# OpenBook_v28.net
KiCad netlist of a schematic drawn in EAGLE
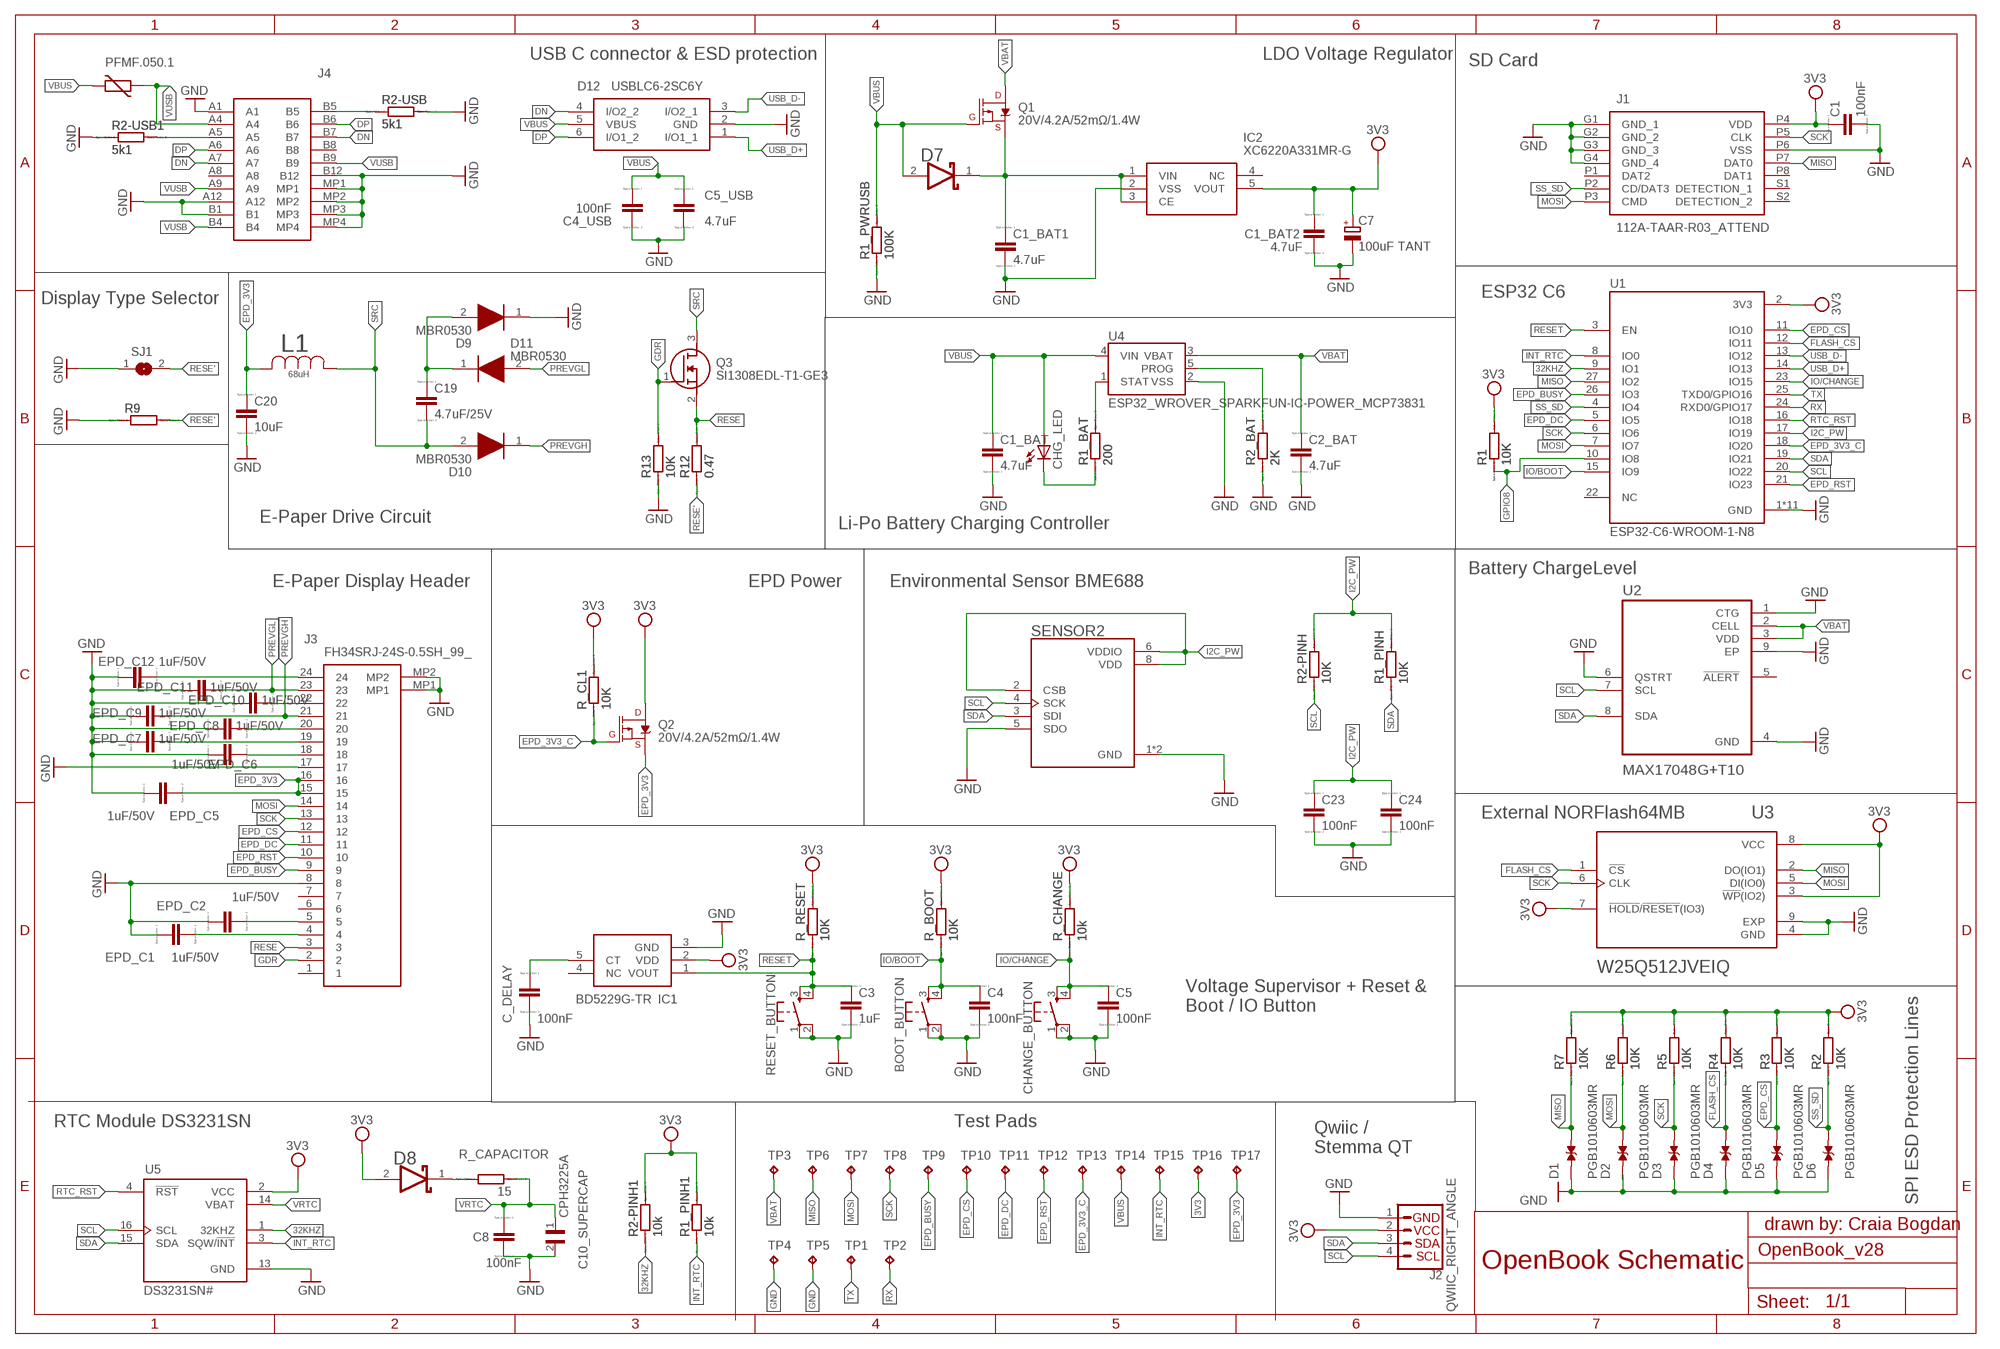
[diagram p0: schematic, sheet 1]

(export (version "E")
  (design (tool "Eeschema 10.0.6"))
  (components
    (comp (ref "BOOT_BUTTON")
      (value "BUTTON_CUSYOMV1")
      (footprint "eagle-import:MYBUTTON")
      (libsource (lib "eagle-import") (part "BUTTON_CUSYOMV1"))
    )
    (comp (ref "C1")
      (value "100nF")
      (footprint "eagle-import:EAGLE-LTSPICE_C0402")
      (libsource (lib "eagle-import") (part "EAGLE-LTSPICE_CC0402"))
    )
    (comp (ref "C1_BAT")
      (value "4.7uF")
      (footprint "eagle-import:EAGLE-LTSPICE_C0402")
      (libsource (lib "eagle-import") (part "EAGLE-LTSPICE_CC0402"))
    )
    (comp (ref "C1_BAT1")
      (value "4.7uF")
      (footprint "eagle-import:EAGLE-LTSPICE_C0402")
      (libsource (lib "eagle-import") (part "EAGLE-LTSPICE_CC0402"))
    )
    (comp (ref "C1_BAT2")
      (value "4.7uF")
      (footprint "eagle-import:EAGLE-LTSPICE_C0402")
      (libsource (lib "eagle-import") (part "EAGLE-LTSPICE_CC0402"))
    )
    (comp (ref "C2_BAT")
      (value "4.7uF")
      (footprint "eagle-import:EAGLE-LTSPICE_C0402")
      (libsource (lib "eagle-import") (part "EAGLE-LTSPICE_CC0402"))
    )
    (comp (ref "C3")
      (value "1uF")
      (footprint "eagle-import:EAGLE-LTSPICE_C0402")
      (libsource (lib "eagle-import") (part "EAGLE-LTSPICE_CC0402"))
    )
    (comp (ref "C4")
      (value "100nF")
      (footprint "eagle-import:EAGLE-LTSPICE_C0402")
      (libsource (lib "eagle-import") (part "EAGLE-LTSPICE_CC0402"))
    )
    (comp (ref "C4_USB")
      (value "100nF")
      (footprint "eagle-import:EAGLE-LTSPICE_C0402")
      (libsource (lib "eagle-import") (part "EAGLE-LTSPICE_CC0402"))
    )
    (comp (ref "C5")
      (value "100nF")
      (footprint "eagle-import:EAGLE-LTSPICE_C0402")
      (libsource (lib "eagle-import") (part "EAGLE-LTSPICE_CC0402"))
    )
    (comp (ref "C5_USB")
      (value "4.7uF")
      (footprint "eagle-import:EAGLE-LTSPICE_C0402")
      (libsource (lib "eagle-import") (part "EAGLE-LTSPICE_CC0402"))
    )
    (comp (ref "C7")
      (value "100uF TANT")
      (footprint "eagle-import:RCL_CT3528")
      (libsource (lib "eagle-import") (part "RCL_CPOL-EUCT3528"))
    )
    (comp (ref "C8")
      (value "100nF")
      (footprint "eagle-import:EAGLE-LTSPICE_C0402")
      (libsource (lib "eagle-import") (part "EAGLE-LTSPICE_CC0402"))
    )
    (comp (ref "C10_SUPERCAP")
      (value "CPH3225A")
      (footprint "eagle-import:CAPCP3225X100N")
      (fields (field (name "MF") "Seiko Instruments"))
      (libsource (lib "eagle-import") (part "CPH3225A"))
    )
    (comp (ref "C19")
      (value "4.7uF/25V")
      (footprint "eagle-import:EAGLE-LTSPICE_C0402")
      (libsource (lib "eagle-import") (part "EAGLE-LTSPICE_CC0402"))
    )
    (comp (ref "C20")
      (value "10uF")
      (footprint "eagle-import:EAGLE-LTSPICE_C0402")
      (libsource (lib "eagle-import") (part "EAGLE-LTSPICE_CC0402"))
    )
    (comp (ref "C23")
      (value "100nF")
      (footprint "eagle-import:EAGLE-LTSPICE_C0402")
      (libsource (lib "eagle-import") (part "EAGLE-LTSPICE_CC0402"))
    )
    (comp (ref "C24")
      (value "100nF")
      (footprint "eagle-import:EAGLE-LTSPICE_C0402")
      (libsource (lib "eagle-import") (part "EAGLE-LTSPICE_CC0402"))
    )
    (comp (ref "CHANGE_BUTTON")
      (value "BUTTON_CUSYOMV1")
      (footprint "eagle-import:MYBUTTON")
      (libsource (lib "eagle-import") (part "BUTTON_CUSYOMV1"))
    )
    (comp (ref "CHG_LED")
      (value "ADAFRUIT_LEDCHIP-LED0603")
      (footprint "eagle-import:ADAFRUIT_CHIP-LED0603")
      (libsource (lib "eagle-import") (part "ADAFRUIT_LEDCHIP-LED0603"))
    )
    (comp (ref "C_DELAY")
      (value "100nF")
      (footprint "eagle-import:EAGLE-LTSPICE_C0402")
      (libsource (lib "eagle-import") (part "EAGLE-LTSPICE_CC0402"))
    )
    (comp (ref "D1")
      (value "PGB1010603MR")
      (footprint "eagle-import:DIOC1608X36N")
      (fields (field (name "MF") "Littelfuse Inc."))
      (libsource (lib "eagle-import") (part "PGB1010603MR"))
    )
    (comp (ref "D2")
      (value "PGB1010603MR")
      (footprint "eagle-import:DIOC1608X36N")
      (fields (field (name "MF") "Littelfuse Inc."))
      (libsource (lib "eagle-import") (part "PGB1010603MR"))
    )
    (comp (ref "D3")
      (value "PGB1010603MR")
      (footprint "eagle-import:DIOC1608X36N")
      (fields (field (name "MF") "Littelfuse Inc."))
      (libsource (lib "eagle-import") (part "PGB1010603MR"))
    )
    (comp (ref "D4")
      (value "PGB1010603MR")
      (footprint "eagle-import:DIOC1608X36N")
      (fields (field (name "MF") "Littelfuse Inc."))
      (libsource (lib "eagle-import") (part "PGB1010603MR"))
    )
    (comp (ref "D5")
      (value "PGB1010603MR")
      (footprint "eagle-import:DIOC1608X36N")
      (fields (field (name "MF") "Littelfuse Inc."))
      (libsource (lib "eagle-import") (part "PGB1010603MR"))
    )
    (comp (ref "D6")
      (value "PGB1010603MR")
      (footprint "eagle-import:DIOC1608X36N")
      (fields (field (name "MF") "Littelfuse Inc."))
      (libsource (lib "eagle-import") (part "PGB1010603MR"))
    )
    (comp (ref "D7")
      (value "ESP32_WROVER_AVX---SD0805S020S1R0_AVX_SD0805S020S1R0_0_0AVX_SD0805S020S1R0_0_0")
      (footprint "eagle-import:ESP32_WROVER_AVX---SD0805S020S1R0_AVX_SD0805S020S1R0_0")
      (fields
        (field (name "DIGIKEY_PART_NUMBER") "478-7800-1-ND")
        (field (name "MF") "AVX")
        (field (name "MOUSER_PART_NUMBER") "581-SD0805S020S1R0")
      )
      (libsource (lib "eagle-import") (part "ESP32_WROVER_AVX---SD0805S020S1R0_AVX_SD0805S020S1R0_0_0AVX_SD0805S020S1R0_0_0"))
    )
    (comp (ref "D8")
      (value "ESP32_WROVER_AVX---SD0805S020S1R0_AVX_SD0805S020S1R0_0_0AVX_SD0805S020S1R0_0_0")
      (footprint "eagle-import:ESP32_WROVER_AVX---SD0805S020S1R0_AVX_SD0805S020S1R0_0")
      (fields
        (field (name "DIGIKEY_PART_NUMBER") "478-7800-1-ND")
        (field (name "MF") "AVX")
        (field (name "MOUSER_PART_NUMBER") "581-SD0805S020S1R0")
      )
      (libsource (lib "eagle-import") (part "ESP32_WROVER_AVX---SD0805S020S1R0_AVX_SD0805S020S1R0_0_0AVX_SD0805S020S1R0_0_0"))
    )
    (comp (ref "D9")
      (value "MBR0530")
      (footprint "eagle-import:SOD3716X135N")
      (fields (field (name "MF") "ON Semiconductor"))
      (libsource (lib "eagle-import") (part "MBR0530"))
    )
    (comp (ref "D10")
      (value "MBR0530")
      (footprint "eagle-import:SOD3716X135N")
      (fields (field (name "MF") "ON Semiconductor"))
      (libsource (lib "eagle-import") (part "MBR0530"))
    )
    (comp (ref "D11")
      (value "MBR0530")
      (footprint "eagle-import:SOD3716X135N")
      (fields (field (name "MF") "ON Semiconductor"))
      (libsource (lib "eagle-import") (part "MBR0530"))
    )
    (comp (ref "D12")
      (value "USBLC6-2SC6Y")
      (footprint "eagle-import:SOT95P280X145-6N")
      (fields (field (name "MF") "STMicroelectronics"))
      (libsource (lib "eagle-import") (part "USBLC6-2SC6Y"))
    )
    (comp (ref "EPD_C1")
      (value "1uF/50V")
      (footprint "eagle-import:EAGLE-LTSPICE_C0402")
      (libsource (lib "eagle-import") (part "EAGLE-LTSPICE_CC0402"))
    )
    (comp (ref "EPD_C2")
      (value "1uF/50V")
      (footprint "eagle-import:EAGLE-LTSPICE_C0402")
      (libsource (lib "eagle-import") (part "EAGLE-LTSPICE_CC0402"))
    )
    (comp (ref "EPD_C5")
      (value "1uF/50V")
      (footprint "eagle-import:EAGLE-LTSPICE_C0402")
      (libsource (lib "eagle-import") (part "EAGLE-LTSPICE_CC0402"))
    )
    (comp (ref "EPD_C6")
      (value "1uF/50V")
      (footprint "eagle-import:EAGLE-LTSPICE_C0402")
      (libsource (lib "eagle-import") (part "EAGLE-LTSPICE_CC0402"))
    )
    (comp (ref "EPD_C7")
      (value "1uF/50V")
      (footprint "eagle-import:EAGLE-LTSPICE_C0402")
      (libsource (lib "eagle-import") (part "EAGLE-LTSPICE_CC0402"))
    )
    (comp (ref "EPD_C8")
      (value "1uF/50V")
      (footprint "eagle-import:EAGLE-LTSPICE_C0402")
      (libsource (lib "eagle-import") (part "EAGLE-LTSPICE_CC0402"))
    )
    (comp (ref "EPD_C9")
      (value "1uF/50V")
      (footprint "eagle-import:EAGLE-LTSPICE_C0402")
      (libsource (lib "eagle-import") (part "EAGLE-LTSPICE_CC0402"))
    )
    (comp (ref "EPD_C10")
      (value "1uF/50V")
      (footprint "eagle-import:EAGLE-LTSPICE_C0402")
      (libsource (lib "eagle-import") (part "EAGLE-LTSPICE_CC0402"))
    )
    (comp (ref "EPD_C11")
      (value "1uF/50V")
      (footprint "eagle-import:EAGLE-LTSPICE_C0402")
      (libsource (lib "eagle-import") (part "EAGLE-LTSPICE_CC0402"))
    )
    (comp (ref "EPD_C12")
      (value "1uF/50V")
      (footprint "eagle-import:EAGLE-LTSPICE_C0402")
      (libsource (lib "eagle-import") (part "EAGLE-LTSPICE_CC0402"))
    )
    (comp (ref "IC1")
      (value "BD5229G-TR")
      (footprint "eagle-import:SOT95P280X125-5N")
      (fields (field (name "MOUSER_PART_NUMBER") "755-BD5229G-TR"))
      (libsource (lib "eagle-import") (part "BD5229G-TR"))
    )
    (comp (ref "IC2")
      (value "XC6220A331MR-G")
      (footprint "eagle-import:SOT95P280X120-5N")
      (fields (field (name "MOUSER_PART_NUMBER") "865-XC6220A331MR-G"))
      (libsource (lib "eagle-import") (part "XC6220A331MR-G"))
    )
    (comp (ref "J1")
      (value "112A-TAAR-R03_ATTEND")
      (footprint "eagle-import:112ATAARR03ATTEND")
      (fields (field (name "MANUFACTURER_PART_NUMBER") "112A-TAAR-R03 ATTEND"))
      (libsource (lib "eagle-import") (part "112A-TAAR-R03_ATTEND"))
    )
    (comp (ref "J2")
      (value "QWIIC_RIGHT_ANGLE")
      (footprint "eagle-import:JST04_1MM_RA")
      (libsource (lib "eagle-import") (part "QWIIC_CONNECTORJS-1MM"))
    )
    (comp (ref "J3")
      (value "FH34SRJ-24S-0.5SH_99_")
      (footprint "eagle-import:FH34SRJ24S05SH99")
      (fields
        (field (name "MANUFACTURER_PART_NUMBER") "FH34SRJ-24S-0.5SH(99)")
        (field (name "MOUSER_PART_NUMBER") "798-FH34SRJ24S05SH99")
      )
      (libsource (lib "eagle-import") (part "FH34SRJ-24S-0.5SH_99_"))
    )
    (comp (ref "J4")
      (value "SAMACSYS_PARTS_USB4110-GF-A")
      (footprint "eagle-import:SAMACSYS_PARTS_USB4110GFA")
      (fields
        (field (name "MANUFACTURER_PART_NUMBER") "USB4110-GF-A")
        (field (name "MOUSER_PART_NUMBER") "640-USB4110-GF-A")
      )
      (libsource (lib "eagle-import") (part "SAMACSYS_PARTS_USB4110-GF-A"))
    )
    (comp (ref "L1")
      (value "68uH")
      (footprint "eagle-import:IND_4828-WE-TPC_WRE")
      (fields
        (field (name "MANUFACTURER_PART_NUMBER") "744043680")
        (field (name "COPYRIGHT") "Copyright (C) 2024 Ultra Librarian. All rights reserved.")
      )
      (libsource (lib "eagle-import") (part "744043680IND_4828-WE-TPC_WRE"))
    )
    (comp (ref "PFMF.050.1")
      (value "ESP32C6_VARISTORCN1812")
      (footprint "eagle-import:ESP32C6_VARISTOR_CT_CN1812")
      (libsource (lib "eagle-import") (part "ESP32C6_VARISTORCN1812"))
    )
    (comp (ref "Q1")
      (value "20V/4.2A/52mΩ/1.4W")
      (footprint "eagle-import:ESP32_WROVER_SPARKFUN-DISCRETESEMI_SOT23-3")
      (libsource (lib "eagle-import") (part "ESP32_WROVER_SPARKFUN-DISCRETESEMI_MOSFET_PCH-DMG2305UX-7"))
    )
    (comp (ref "Q2")
      (value "20V/4.2A/52mΩ/1.4W")
      (footprint "eagle-import:ESP32_WROVER_SPARKFUN-DISCRETESEMI_SOT23-3")
      (libsource (lib "eagle-import") (part "ESP32_WROVER_SPARKFUN-DISCRETESEMI_MOSFET_PCH-DMG2305UX-7"))
    )
    (comp (ref "Q3")
      (value "SI1308EDL-T1-GE3")
      (footprint "eagle-import:SOT65P210X110-3N")
      (fields (field (name "MF") "Vishay Siliconix"))
      (libsource (lib "eagle-import") (part "SI1308EDL-T1-GE3"))
    )
    (comp (ref "R1")
      (value "10K")
      (footprint "eagle-import:ESP32_WROVER_EAGLE-LTSPICE_R0402")
      (libsource (lib "eagle-import") (part "ESP32_WROVER_EAGLE-LTSPICE_RR0402"))
    )
    (comp (ref "R1_BAT")
      (value "200")
      (footprint "eagle-import:ESP32_WROVER_EAGLE-LTSPICE_R0402")
      (libsource (lib "eagle-import") (part "ESP32_WROVER_EAGLE-LTSPICE_RR0402"))
    )
    (comp (ref "R1_PINH")
      (value "10K")
      (footprint "eagle-import:ESP32_WROVER_EAGLE-LTSPICE_R0402")
      (libsource (lib "eagle-import") (part "ESP32_WROVER_EAGLE-LTSPICE_RR0402"))
    )
    (comp (ref "R1_PINH1")
      (value "10k")
      (footprint "eagle-import:ESP32_WROVER_EAGLE-LTSPICE_R0402")
      (libsource (lib "eagle-import") (part "ESP32_WROVER_EAGLE-LTSPICE_RR0402"))
    )
    (comp (ref "R1_PWRUSB")
      (value "100K")
      (footprint "eagle-import:ESP32_WROVER_EAGLE-LTSPICE_R0402")
      (libsource (lib "eagle-import") (part "ESP32_WROVER_EAGLE-LTSPICE_RR0402"))
    )
    (comp (ref "R2")
      (value "10K")
      (footprint "eagle-import:ESP32_WROVER_EAGLE-LTSPICE_R0402")
      (libsource (lib "eagle-import") (part "ESP32_WROVER_EAGLE-LTSPICE_RR0402"))
    )
    (comp (ref "R2-PINH")
      (value "10K")
      (footprint "eagle-import:ESP32_WROVER_EAGLE-LTSPICE_R0402")
      (libsource (lib "eagle-import") (part "ESP32_WROVER_EAGLE-LTSPICE_RR0402"))
    )
    (comp (ref "R2-PINH1")
      (value "10k")
      (footprint "eagle-import:ESP32_WROVER_EAGLE-LTSPICE_R0402")
      (libsource (lib "eagle-import") (part "ESP32_WROVER_EAGLE-LTSPICE_RR0402"))
    )
    (comp (ref "R2-USB")
      (value "5k1")
      (footprint "eagle-import:ESP32_WROVER_EAGLE-LTSPICE_R0402")
      (libsource (lib "eagle-import") (part "ESP32_WROVER_EAGLE-LTSPICE_RR0402"))
    )
    (comp (ref "R2-USB1")
      (value "5k1")
      (footprint "eagle-import:ESP32_WROVER_EAGLE-LTSPICE_R0402")
      (libsource (lib "eagle-import") (part "ESP32_WROVER_EAGLE-LTSPICE_RR0402"))
    )
    (comp (ref "R2_BAT")
      (value "2K")
      (footprint "eagle-import:ESP32_WROVER_EAGLE-LTSPICE_R0402")
      (libsource (lib "eagle-import") (part "ESP32_WROVER_EAGLE-LTSPICE_RR0402"))
    )
    (comp (ref "R3")
      (value "10K")
      (footprint "eagle-import:ESP32_WROVER_EAGLE-LTSPICE_R0402")
      (libsource (lib "eagle-import") (part "ESP32_WROVER_EAGLE-LTSPICE_RR0402"))
    )
    (comp (ref "R4")
      (value "10K")
      (footprint "eagle-import:ESP32_WROVER_EAGLE-LTSPICE_R0402")
      (libsource (lib "eagle-import") (part "ESP32_WROVER_EAGLE-LTSPICE_RR0402"))
    )
    (comp (ref "R5")
      (value "10K")
      (footprint "eagle-import:ESP32_WROVER_EAGLE-LTSPICE_R0402")
      (libsource (lib "eagle-import") (part "ESP32_WROVER_EAGLE-LTSPICE_RR0402"))
    )
    (comp (ref "R6")
      (value "10K")
      (footprint "eagle-import:ESP32_WROVER_EAGLE-LTSPICE_R0402")
      (libsource (lib "eagle-import") (part "ESP32_WROVER_EAGLE-LTSPICE_RR0402"))
    )
    (comp (ref "R7")
      (value "10K")
      (footprint "eagle-import:ESP32_WROVER_EAGLE-LTSPICE_R0402")
      (libsource (lib "eagle-import") (part "ESP32_WROVER_EAGLE-LTSPICE_RR0402"))
    )
    (comp (ref "R9")
      (value "ESP32_WROVER_EAGLE-LTSPICE_RR0402")
      (footprint "eagle-import:ESP32_WROVER_EAGLE-LTSPICE_R0402")
      (libsource (lib "eagle-import") (part "ESP32_WROVER_EAGLE-LTSPICE_RR0402"))
    )
    (comp (ref "R12")
      (value "0.47")
      (footprint "eagle-import:ESP32_WROVER_EAGLE-LTSPICE_R0402")
      (libsource (lib "eagle-import") (part "ESP32_WROVER_EAGLE-LTSPICE_RR0402"))
    )
    (comp (ref "R13")
      (value "10K")
      (footprint "eagle-import:ESP32_WROVER_EAGLE-LTSPICE_R0402")
      (libsource (lib "eagle-import") (part "ESP32_WROVER_EAGLE-LTSPICE_RR0402"))
    )
    (comp (ref "RESET_BUTTON")
      (value "BUTTON_CUSYOMV1")
      (footprint "eagle-import:MYBUTTON")
      (libsource (lib "eagle-import") (part "BUTTON_CUSYOMV1"))
    )
    (comp (ref "R_BOOT")
      (value "10K")
      (footprint "eagle-import:ESP32_WROVER_EAGLE-LTSPICE_R0402")
      (libsource (lib "eagle-import") (part "ESP32_WROVER_EAGLE-LTSPICE_RR0402"))
    )
    (comp (ref "R_CAPACITOR")
      (value "15")
      (footprint "eagle-import:ESP32_WROVER_EAGLE-LTSPICE_R0402")
      (libsource (lib "eagle-import") (part "ESP32_WROVER_EAGLE-LTSPICE_RR0402"))
    )
    (comp (ref "R_CHANGE")
      (value "10k")
      (footprint "eagle-import:ESP32_WROVER_EAGLE-LTSPICE_R0402")
      (libsource (lib "eagle-import") (part "ESP32_WROVER_EAGLE-LTSPICE_RR0402"))
    )
    (comp (ref "R_CL1")
      (value "10K")
      (footprint "eagle-import:ESP32_WROVER_EAGLE-LTSPICE_R0402")
      (libsource (lib "eagle-import") (part "ESP32_WROVER_EAGLE-LTSPICE_RR0402"))
    )
    (comp (ref "R_RESET")
      (value "10K")
      (footprint "eagle-import:ESP32_WROVER_EAGLE-LTSPICE_R0402")
      (libsource (lib "eagle-import") (part "ESP32_WROVER_EAGLE-LTSPICE_RR0402"))
    )
    (comp (ref "SENSOR2")
      (value "ESP32_WROVER_BME680_BME680")
      (footprint "eagle-import:ESP32_WROVER_BME680_PSON80P300X300X100-8N")
      (fields (field (name "MF") "Bosch Sensortec") (field (name "MP") "BME680"))
      (libsource (lib "eagle-import") (part "ESP32_WROVER_BME680_BME680"))
    )
    (comp (ref "SJ1") (value "SJ") (footprint "eagle-import:SJ") (libsource (lib "eagle-import") (part "SJ")))
    (comp (ref "TP1")
      (value "TPTP20R")
      (footprint "eagle-import:TP20R")
      (libsource (lib "eagle-import") (part "TPTP20R"))
    )
    (comp (ref "TP2")
      (value "TPTP20R")
      (footprint "eagle-import:TP20R")
      (libsource (lib "eagle-import") (part "TPTP20R"))
    )
    (comp (ref "TP3")
      (value "TPTP20R")
      (footprint "eagle-import:TP20R")
      (libsource (lib "eagle-import") (part "TPTP20R"))
    )
    (comp (ref "TP4")
      (value "TPTP20R")
      (footprint "eagle-import:TP20R")
      (libsource (lib "eagle-import") (part "TPTP20R"))
    )
    (comp (ref "TP5")
      (value "TPTP20R")
      (footprint "eagle-import:TP20R")
      (libsource (lib "eagle-import") (part "TPTP20R"))
    )
    (comp (ref "TP6")
      (value "TPTP20R")
      (footprint "eagle-import:TP20R")
      (libsource (lib "eagle-import") (part "TPTP20R"))
    )
    (comp (ref "TP7")
      (value "TPTP20R")
      (footprint "eagle-import:TP20R")
      (libsource (lib "eagle-import") (part "TPTP20R"))
    )
    (comp (ref "TP8")
      (value "TPTP20R")
      (footprint "eagle-import:TP20R")
      (libsource (lib "eagle-import") (part "TPTP20R"))
    )
    (comp (ref "TP9")
      (value "TPTP20R")
      (footprint "eagle-import:TP20R")
      (libsource (lib "eagle-import") (part "TPTP20R"))
    )
    (comp (ref "TP10")
      (value "TPTP20R")
      (footprint "eagle-import:TP20R")
      (libsource (lib "eagle-import") (part "TPTP20R"))
    )
    (comp (ref "TP11")
      (value "TPTP20R")
      (footprint "eagle-import:TP20R")
      (libsource (lib "eagle-import") (part "TPTP20R"))
    )
    (comp (ref "TP12")
      (value "TPTP20R")
      (footprint "eagle-import:TP20R")
      (libsource (lib "eagle-import") (part "TPTP20R"))
    )
    (comp (ref "TP13")
      (value "TPTP20R")
      (footprint "eagle-import:TP20R")
      (libsource (lib "eagle-import") (part "TPTP20R"))
    )
    (comp (ref "TP14")
      (value "TPTP20R")
      (footprint "eagle-import:TP20R")
      (libsource (lib "eagle-import") (part "TPTP20R"))
    )
    (comp (ref "TP15")
      (value "TPTP20R")
      (footprint "eagle-import:TP20R")
      (libsource (lib "eagle-import") (part "TPTP20R"))
    )
    (comp (ref "TP16")
      (value "TPTP20R")
      (footprint "eagle-import:TP20R")
      (libsource (lib "eagle-import") (part "TPTP20R"))
    )
    (comp (ref "TP17")
      (value "TPTP20R")
      (footprint "eagle-import:TP20R")
      (libsource (lib "eagle-import") (part "TPTP20R"))
    )
    (comp (ref "U1")
      (value "ESP32-C6-WROOM-1-N8")
      (footprint "eagle-import:XCVR_ESP32-C6-WROOM-1-N8")
      (fields (field (name "MF") "Espressif Systems"))
      (libsource (lib "eagle-import") (part "ESP32-C6-WROOM-1-N8"))
    )
    (comp (ref "U2")
      (value "MAX17048G+T10")
      (footprint "eagle-import:SON50P200X200X80-9N")
      (fields (field (name "MF") "Analog Devices"))
      (libsource (lib "eagle-import") (part "MAX17048G+T10"))
    )
    (comp (ref "U3")
      (value "W25Q512JVEIQ")
      (footprint "eagle-import:SON127P600X800X80-9N")
      (fields (field (name "MF") "Winbond Electronics"))
      (libsource (lib "eagle-import") (part "W25Q512JVEIQ"))
    )
    (comp (ref "U4")
      (value "ESP32_WROVER_SPARKFUN-IC-POWER_MCP73831")
      (footprint "eagle-import:ESP32_WROVER_SPARKFUN-IC-POWER_SOT23-5")
      (libsource (lib "eagle-import") (part "ESP32_WROVER_SPARKFUN-IC-POWER_MCP73831"))
    )
    (comp (ref "U5")
      (value "DS3231SN#")
      (footprint "eagle-import:SOIC127P1032X265-16N")
      (fields (field (name "MF") "Analog Devices"))
      (libsource (lib "eagle-import") (part "DS3231SN#"))
    )
  )
  (nets
    (net (code "1") (name "3V3") (class "Default")
      (node (ref "C1") (pin "1") (pinfunction "1_1") (pintype "passive"))
      (node (ref "C1_BAT2") (pin "1") (pinfunction "1_1") (pintype "passive"))
      (node (ref "C7") (pin "+") (pinfunction "+_+") (pintype "passive"))
      (node (ref "D8") (pin "2") (pinfunction "ANODE_2") (pintype "bidirectional"))
      (node (ref "IC1") (pin "2") (pinfunction "VDD_2") (pintype "bidirectional"))
      (node (ref "IC2") (pin "5") (pinfunction "VOUT_5") (pintype "bidirectional"))
      (node (ref "J1") (pin "P4") (pinfunction "VDD_P4") (pintype "bidirectional"))
      (node (ref "J2") (pin "2") (pinfunction "2_2") (pintype "power_in"))
      (node (ref "Q2") (pin "3") (pinfunction "D_3") (pintype "bidirectional"))
      (node (ref "R1") (pin "2") (pinfunction "2_2") (pintype "passive"))
      (node (ref "R1_PINH1") (pin "2") (pinfunction "2_2") (pintype "passive"))
      (node (ref "R2") (pin "2") (pinfunction "2_2") (pintype "passive"))
      (node (ref "R2-PINH1") (pin "2") (pinfunction "2_2") (pintype "passive"))
      (node (ref "R3") (pin "2") (pinfunction "2_2") (pintype "passive"))
      (node (ref "R4") (pin "2") (pinfunction "2_2") (pintype "passive"))
      (node (ref "R5") (pin "2") (pinfunction "2_2") (pintype "passive"))
      (node (ref "R6") (pin "2") (pinfunction "2_2") (pintype "passive"))
      (node (ref "R7") (pin "2") (pinfunction "2_2") (pintype "passive"))
      (node (ref "R_BOOT") (pin "2") (pinfunction "2_2") (pintype "passive"))
      (node (ref "R_CHANGE") (pin "2") (pinfunction "2_2") (pintype "passive"))
      (node (ref "R_CL1") (pin "2") (pinfunction "2_2") (pintype "passive"))
      (node (ref "R_RESET") (pin "2") (pinfunction "2_2") (pintype "passive"))
      (node (ref "TP16") (pin "TP") (pinfunction "TP_TP") (pintype "input"))
      (node (ref "U1") (pin "2") (pinfunction "3V3_2") (pintype "power_in"))
      (node (ref "U3") (pin "3") (pinfunction "~{WP}(IO2)_3") (pintype "bidirectional"))
      (node (ref "U3") (pin "7") (pinfunction "~{HOLD}/~{RESET}(IO3)_7") (pintype "bidirectional"))
      (node (ref "U3") (pin "8") (pinfunction "VCC_8") (pintype "power_in"))
      (node (ref "U5") (pin "2") (pinfunction "VCC_2") (pintype "power_in"))
    )
    (net (code "2") (name "32KHZ") (class "Default")
      (node (ref "R2-PINH1") (pin "1") (pinfunction "1_1") (pintype "passive"))
      (node (ref "U1") (pin "9") (pinfunction "IO1_9") (pintype "bidirectional"))
      (node (ref "U5") (pin "1") (pinfunction "32KHZ_1") (pintype "output"))
    )
    (net (code "3") (name "DN") (class "Default")
      (node (ref "D12") (pin "4") (pinfunction "I/O2_2_4") (pintype "bidirectional"))
      (node (ref "J4") (pin "A7") (pinfunction "A7_A7") (pintype "bidirectional"))
      (node (ref "J4") (pin "B7") (pinfunction "B7_B7") (pintype "bidirectional"))
    )
    (net (code "4") (name "DP") (class "Default")
      (node (ref "D12") (pin "6") (pinfunction "I/O1_2_6") (pintype "bidirectional"))
      (node (ref "J4") (pin "A6") (pinfunction "A6_A6") (pintype "bidirectional"))
      (node (ref "J4") (pin "B6") (pinfunction "B6_B6") (pintype "bidirectional"))
    )
    (net (code "5") (name "EPD_3V3") (class "Default")
      (node (ref "C20") (pin "1") (pinfunction "1_1") (pintype "passive"))
      (node (ref "EPD_C5") (pin "2") (pinfunction "2_2") (pintype "passive"))
      (node (ref "J3") (pin "15") (pinfunction "15_15") (pintype "bidirectional"))
      (node (ref "J3") (pin "16") (pinfunction "16_16") (pintype "bidirectional"))
      (node (ref "L1") (pin "2") (pinfunction "2_2") (pintype "passive"))
      (node (ref "Q2") (pin "2") (pinfunction "S_2") (pintype "bidirectional"))
      (node (ref "TP17") (pin "TP") (pinfunction "TP_TP") (pintype "input"))
    )
    (net (code "6") (name "EPD_3V3_C") (class "Default")
      (node (ref "Q2") (pin "1") (pinfunction "G_1") (pintype "bidirectional"))
      (node (ref "R_CL1") (pin "1") (pinfunction "1_1") (pintype "passive"))
      (node (ref "TP13") (pin "TP") (pinfunction "TP_TP") (pintype "input"))
      (node (ref "U1") (pin "18") (pinfunction "IO20_18") (pintype "bidirectional"))
    )
    (net (code "7") (name "EPD_BUSY") (class "Default")
      (node (ref "J3") (pin "9") (pinfunction "9_9") (pintype "bidirectional"))
      (node (ref "TP9") (pin "TP") (pinfunction "TP_TP") (pintype "input"))
      (node (ref "U1") (pin "26") (pinfunction "IO3_26") (pintype "bidirectional"))
    )
    (net (code "8") (name "EPD_CS") (class "Default")
      (node (ref "D5") (pin "2") (pinfunction "2_2") (pintype "passive"))
      (node (ref "J3") (pin "12") (pinfunction "12_12") (pintype "bidirectional"))
      (node (ref "R3") (pin "1") (pinfunction "1_1") (pintype "passive"))
      (node (ref "TP10") (pin "TP") (pinfunction "TP_TP") (pintype "input"))
      (node (ref "U1") (pin "11") (pinfunction "IO10_11") (pintype "bidirectional"))
    )
    (net (code "9") (name "EPD_DC") (class "Default")
      (node (ref "J3") (pin "11") (pinfunction "11_11") (pintype "bidirectional"))
      (node (ref "TP11") (pin "TP") (pinfunction "TP_TP") (pintype "input"))
      (node (ref "U1") (pin "5") (pinfunction "IO5_5") (pintype "bidirectional"))
    )
    (net (code "10") (name "EPD_RST") (class "Default")
      (node (ref "J3") (pin "10") (pinfunction "10_10") (pintype "bidirectional"))
      (node (ref "TP12") (pin "TP") (pinfunction "TP_TP") (pintype "input"))
      (node (ref "U1") (pin "21") (pinfunction "IO23_21") (pintype "bidirectional"))
    )
    (net (code "11") (name "FLASH_CS") (class "Default")
      (node (ref "D4") (pin "2") (pinfunction "2_2") (pintype "passive"))
      (node (ref "R4") (pin "1") (pinfunction "1_1") (pintype "passive"))
      (node (ref "U1") (pin "12") (pinfunction "IO11_12") (pintype "bidirectional"))
      (node (ref "U3") (pin "1") (pinfunction "~{CS}_1") (pintype "input"))
    )
    (net (code "12") (name "GDR") (class "Default")
      (node (ref "J3") (pin "2") (pinfunction "2_2") (pintype "bidirectional"))
      (node (ref "Q3") (pin "1") (pinfunction "G_1") (pintype "bidirectional"))
      (node (ref "R13") (pin "2") (pinfunction "2_2") (pintype "passive"))
    )
    (net (code "13") (name "GND") (class "Default")
      (node (ref "BOOT_BUTTON") (pin "1") (pinfunction "1_1") (pintype "passive"))
      (node (ref "BOOT_BUTTON") (pin "2") (pinfunction "2_2") (pintype "passive"))
      (node (ref "C1") (pin "2") (pinfunction "2_2") (pintype "passive"))
      (node (ref "C10_SUPERCAP") (pin "2") (pinfunction "2_2") (pintype "passive"))
      (node (ref "C1_BAT") (pin "2") (pinfunction "2_2") (pintype "passive"))
      (node (ref "C1_BAT1") (pin "2") (pinfunction "2_2") (pintype "passive"))
      (node (ref "C1_BAT2") (pin "2") (pinfunction "2_2") (pintype "passive"))
      (node (ref "C20") (pin "2") (pinfunction "2_2") (pintype "passive"))
      (node (ref "C23") (pin "2") (pinfunction "2_2") (pintype "passive"))
      (node (ref "C24") (pin "2") (pinfunction "2_2") (pintype "passive"))
      (node (ref "C2_BAT") (pin "2") (pinfunction "2_2") (pintype "passive"))
      (node (ref "C3") (pin "2") (pinfunction "2_2") (pintype "passive"))
      (node (ref "C4") (pin "2") (pinfunction "2_2") (pintype "passive"))
      (node (ref "C4_USB") (pin "2") (pinfunction "2_2") (pintype "passive"))
      (node (ref "C5") (pin "2") (pinfunction "2_2") (pintype "passive"))
      (node (ref "C5_USB") (pin "2") (pinfunction "2_2") (pintype "passive"))
      (node (ref "C7") (pin "-") (pinfunction "-_-") (pintype "passive"))
      (node (ref "C8") (pin "2") (pinfunction "2_2") (pintype "passive"))
      (node (ref "CHANGE_BUTTON") (pin "1") (pinfunction "1_1") (pintype "passive"))
      (node (ref "CHANGE_BUTTON") (pin "2") (pinfunction "2_2") (pintype "passive"))
      (node (ref "C_DELAY") (pin "2") (pinfunction "2_2") (pintype "passive"))
      (node (ref "D1") (pin "1") (pinfunction "1_1") (pintype "passive"))
      (node (ref "D12") (pin "2") (pinfunction "GND_2") (pintype "bidirectional"))
      (node (ref "D2") (pin "1") (pinfunction "1_1") (pintype "passive"))
      (node (ref "D3") (pin "1") (pinfunction "1_1") (pintype "passive"))
      (node (ref "D4") (pin "1") (pinfunction "1_1") (pintype "passive"))
      (node (ref "D5") (pin "1") (pinfunction "1_1") (pintype "passive"))
      (node (ref "D6") (pin "1") (pinfunction "1_1") (pintype "passive"))
      (node (ref "D9") (pin "1") (pinfunction "K_1") (pintype "bidirectional"))
      (node (ref "EPD_C1") (pin "1") (pinfunction "1_1") (pintype "passive"))
      (node (ref "EPD_C10") (pin "1") (pinfunction "1_1") (pintype "passive"))
      (node (ref "EPD_C11") (pin "1") (pinfunction "1_1") (pintype "passive"))
      (node (ref "EPD_C12") (pin "1") (pinfunction "1_1") (pintype "passive"))
      (node (ref "EPD_C2") (pin "1") (pinfunction "1_1") (pintype "passive"))
      (node (ref "EPD_C5") (pin "1") (pinfunction "1_1") (pintype "passive"))
      (node (ref "EPD_C6") (pin "1") (pinfunction "1_1") (pintype "passive"))
      (node (ref "EPD_C7") (pin "1") (pinfunction "1_1") (pintype "passive"))
      (node (ref "EPD_C8") (pin "1") (pinfunction "1_1") (pintype "passive"))
      (node (ref "EPD_C9") (pin "1") (pinfunction "1_1") (pintype "passive"))
      (node (ref "IC1") (pin "3") (pinfunction "GND_3") (pintype "bidirectional"))
      (node (ref "IC2") (pin "2") (pinfunction "VSS_2") (pintype "bidirectional"))
      (node (ref "J1") (pin "G1") (pinfunction "GND_1_G1") (pintype "bidirectional"))
      (node (ref "J1") (pin "G2") (pinfunction "GND_2_G2") (pintype "bidirectional"))
      (node (ref "J1") (pin "G3") (pinfunction "GND_3_G3") (pintype "bidirectional"))
      (node (ref "J1") (pin "G4") (pinfunction "GND_4_G4") (pintype "bidirectional"))
      (node (ref "J1") (pin "P6") (pinfunction "VSS_P6") (pintype "bidirectional"))
      (node (ref "J2") (pin "1") (pinfunction "1_1") (pintype "power_in"))
      (node (ref "J3") (pin "17") (pinfunction "17_17") (pintype "bidirectional"))
      (node (ref "J3") (pin "8") (pinfunction "8_8") (pintype "bidirectional"))
      (node (ref "J3") (pin "MP1") (pinfunction "MP1_MP1") (pintype "bidirectional"))
      (node (ref "J3") (pin "MP2") (pinfunction "MP2_MP2") (pintype "bidirectional"))
      (node (ref "J4") (pin "A1") (pinfunction "A1_A1") (pintype "bidirectional"))
      (node (ref "J4") (pin "A12") (pinfunction "A12_A12") (pintype "bidirectional"))
      (node (ref "J4") (pin "B1") (pinfunction "B1_B1") (pintype "bidirectional"))
      (node (ref "J4") (pin "B12") (pinfunction "B12_B12") (pintype "bidirectional"))
      (node (ref "J4") (pin "MP1") (pinfunction "MP1_MP1") (pintype "bidirectional"))
      (node (ref "J4") (pin "MP2") (pinfunction "MP2_MP2") (pintype "bidirectional"))
      (node (ref "J4") (pin "MP3") (pinfunction "MP3_MP3") (pintype "bidirectional"))
      (node (ref "J4") (pin "MP4") (pinfunction "MP4_MP4") (pintype "bidirectional"))
      (node (ref "R13") (pin "1") (pinfunction "1_1") (pintype "passive"))
      (node (ref "R1_PWRUSB") (pin "1") (pinfunction "1_1") (pintype "passive"))
      (node (ref "R2-USB") (pin "2") (pinfunction "2_2") (pintype "passive"))
      (node (ref "R2-USB1") (pin "1") (pinfunction "1_1") (pintype "passive"))
      (node (ref "R2_BAT") (pin "1") (pinfunction "1_1") (pintype "passive"))
      (node (ref "R9") (pin "1") (pinfunction "1_1") (pintype "passive"))
      (node (ref "RESET_BUTTON") (pin "1") (pinfunction "1_1") (pintype "passive"))
      (node (ref "RESET_BUTTON") (pin "2") (pinfunction "2_2") (pintype "passive"))
      (node (ref "SENSOR2") (pin "1") (pinfunction "GND_1") (pintype "power_in"))
      (node (ref "SENSOR2") (pin "5") (pinfunction "SDO_5") (pintype "bidirectional"))
      (node (ref "SENSOR2") (pin "7") (pinfunction "GND_7") (pintype "power_in"))
      (node (ref "SJ1") (pin "1") (pinfunction "1_1") (pintype "passive"))
      (node (ref "TP4") (pin "TP") (pinfunction "TP_TP") (pintype "input"))
      (node (ref "TP5") (pin "TP") (pinfunction "TP_TP") (pintype "input"))
      (node (ref "U1") (pin "1") (pinfunction "GND_1") (pintype "power_in"))
      (node (ref "U1") (pin "28") (pinfunction "GND_28") (pintype "power_in"))
      (node (ref "U1") (pin "29_1") (pinfunction "GND_29_1") (pintype "power_in"))
      (node (ref "U1") (pin "29_2") (pinfunction "GND_29_2") (pintype "power_in"))
      (node (ref "U1") (pin "29_3") (pinfunction "GND_29_3") (pintype "power_in"))
      (node (ref "U1") (pin "29_4") (pinfunction "GND_29_4") (pintype "power_in"))
      (node (ref "U1") (pin "29_5") (pinfunction "GND_29_5") (pintype "power_in"))
      (node (ref "U1") (pin "29_6") (pinfunction "GND_29_6") (pintype "power_in"))
      (node (ref "U1") (pin "29_7") (pinfunction "GND_29_7") (pintype "power_in"))
      (node (ref "U1") (pin "29_8") (pinfunction "GND_29_8") (pintype "power_in"))
      (node (ref "U1") (pin "29_9") (pinfunction "GND_29_9") (pintype "power_in"))
      (node (ref "U2") (pin "1") (pinfunction "CTG_1") (pintype "power_in"))
      (node (ref "U2") (pin "4") (pinfunction "GND_4") (pintype "power_in"))
      (node (ref "U2") (pin "6") (pinfunction "QSTRT_6") (pintype "input"))
      (node (ref "U2") (pin "9") (pinfunction "EP_9") (pintype "power_in"))
      (node (ref "U3") (pin "4") (pinfunction "GND_4") (pintype "power_in"))
      (node (ref "U3") (pin "9") (pinfunction "EXP_9") (pintype "passive"))
      (node (ref "U4") (pin "2") (pinfunction "VSS_2") (pintype "power_in"))
      (node (ref "U5") (pin "13") (pinfunction "GND_13") (pintype "power_in"))
    )
    (net (code "14") (name "GPIO8") (class "Default")
      (node (ref "R1") (pin "1") (pinfunction "1_1") (pintype "passive"))
      (node (ref "U1") (pin "10") (pinfunction "IO8_10") (pintype "bidirectional"))
    )
    (net (code "15") (name "I2C_PW") (class "Default")
      (node (ref "C23") (pin "1") (pinfunction "1_1") (pintype "passive"))
      (node (ref "C24") (pin "1") (pinfunction "1_1") (pintype "passive"))
      (node (ref "R1_PINH") (pin "2") (pinfunction "2_2") (pintype "passive"))
      (node (ref "R2-PINH") (pin "2") (pinfunction "2_2") (pintype "passive"))
      (node (ref "SENSOR2") (pin "2") (pinfunction "CSB_2") (pintype "input"))
      (node (ref "SENSOR2") (pin "6") (pinfunction "VDDIO_6") (pintype "power_in"))
      (node (ref "SENSOR2") (pin "8") (pinfunction "VDD_8") (pintype "power_in"))
      (node (ref "U1") (pin "17") (pinfunction "IO19_17") (pintype "bidirectional"))
    )
    (net (code "16") (name "INT_RTC") (class "Default")
      (node (ref "R1_PINH1") (pin "1") (pinfunction "1_1") (pintype "passive"))
      (node (ref "TP15") (pin "TP") (pinfunction "TP_TP") (pintype "input"))
      (node (ref "U1") (pin "8") (pinfunction "IO0_8") (pintype "bidirectional"))
      (node (ref "U5") (pin "3") (pinfunction "SQW/~{INT}_3") (pintype "output"))
    )
    (net (code "17") (name "IO{slash}BOOT") (class "Default")
      (node (ref "BOOT_BUTTON") (pin "3") (pinfunction "3_3") (pintype "passive"))
      (node (ref "BOOT_BUTTON") (pin "4") (pinfunction "4_4") (pintype "passive"))
      (node (ref "C4") (pin "1") (pinfunction "1_1") (pintype "passive"))
      (node (ref "R_BOOT") (pin "1") (pinfunction "1_1") (pintype "passive"))
      (node (ref "U1") (pin "15") (pinfunction "IO9_15") (pintype "bidirectional"))
    )
    (net (code "18") (name "IO{slash}CHANGE") (class "Default")
      (node (ref "C5") (pin "1") (pinfunction "1_1") (pintype "passive"))
      (node (ref "CHANGE_BUTTON") (pin "3") (pinfunction "3_3") (pintype "passive"))
      (node (ref "CHANGE_BUTTON") (pin "4") (pinfunction "4_4") (pintype "passive"))
      (node (ref "R_CHANGE") (pin "1") (pinfunction "1_1") (pintype "passive"))
      (node (ref "U1") (pin "23") (pinfunction "IO15_23") (pintype "bidirectional"))
    )
    (net (code "19") (name "MISO") (class "Default")
      (node (ref "D1") (pin "2") (pinfunction "2_2") (pintype "passive"))
      (node (ref "J1") (pin "P7") (pinfunction "DAT0_P7") (pintype "bidirectional"))
      (node (ref "R7") (pin "1") (pinfunction "1_1") (pintype "passive"))
      (node (ref "TP6") (pin "TP") (pinfunction "TP_TP") (pintype "input"))
      (node (ref "U1") (pin "27") (pinfunction "IO2_27") (pintype "bidirectional"))
      (node (ref "U3") (pin "2") (pinfunction "DO(IO1)_2") (pintype "bidirectional"))
    )
    (net (code "20") (name "MOSI") (class "Default")
      (node (ref "D2") (pin "2") (pinfunction "2_2") (pintype "passive"))
      (node (ref "J1") (pin "P3") (pinfunction "CMD_P3") (pintype "bidirectional"))
      (node (ref "J3") (pin "14") (pinfunction "14_14") (pintype "bidirectional"))
      (node (ref "R6") (pin "1") (pinfunction "1_1") (pintype "passive"))
      (node (ref "TP7") (pin "TP") (pinfunction "TP_TP") (pintype "input"))
      (node (ref "U1") (pin "7") (pinfunction "IO7_7") (pintype "bidirectional"))
      (node (ref "U3") (pin "5") (pinfunction "DI(IO0)_5") (pintype "bidirectional"))
    )
    (net (code "21") (name "Net-(CHG_LED-PadC)") (class "Default")
      (node (ref "CHG_LED") (pin "C") (pinfunction "C_C") (pintype "passive"))
      (node (ref "R1_BAT") (pin "1") (pinfunction "1_1") (pintype "passive"))
    )
    (net (code "22") (name "Net-(D7-CATHODE)") (class "Default")
      (node (ref "C1_BAT1") (pin "1") (pinfunction "1_1") (pintype "passive"))
      (node (ref "D7") (pin "1") (pinfunction "CATHODE_1") (pintype "bidirectional"))
      (node (ref "IC2") (pin "1") (pinfunction "VIN_1") (pintype "bidirectional"))
      (node (ref "IC2") (pin "3") (pinfunction "CE_3") (pintype "bidirectional"))
      (node (ref "Q1") (pin "2") (pinfunction "S_2") (pintype "bidirectional"))
    )
    (net (code "23") (name "Net-(D8-CATHODE)") (class "Default")
      (node (ref "D8") (pin "1") (pinfunction "CATHODE_1") (pintype "bidirectional"))
      (node (ref "R_CAPACITOR") (pin "1") (pinfunction "1_1") (pintype "passive"))
    )
    (net (code "24") (name "Net-(D11-K)") (class "Default")
      (node (ref "C19") (pin "1") (pinfunction "1_1") (pintype "passive"))
      (node (ref "D11") (pin "1") (pinfunction "K_1") (pintype "bidirectional"))
      (node (ref "D9") (pin "2") (pinfunction "A_2") (pintype "bidirectional"))
    )
    (net (code "25") (name "Net-(EPD_C1-Pad2)") (class "Default")
      (node (ref "EPD_C1") (pin "2") (pinfunction "2_2") (pintype "passive"))
      (node (ref "J3") (pin "4") (pinfunction "4_4") (pintype "bidirectional"))
    )
    (net (code "26") (name "Net-(EPD_C2-Pad2)") (class "Default")
      (node (ref "EPD_C2") (pin "2") (pinfunction "2_2") (pintype "passive"))
      (node (ref "J3") (pin "5") (pinfunction "5_5") (pintype "bidirectional"))
    )
    (net (code "27") (name "Net-(EPD_C6-Pad2)") (class "Default")
      (node (ref "EPD_C6") (pin "2") (pinfunction "2_2") (pintype "passive"))
      (node (ref "J3") (pin "18") (pinfunction "18_18") (pintype "bidirectional"))
    )
    (net (code "28") (name "Net-(EPD_C7-Pad2)") (class "Default")
      (node (ref "EPD_C7") (pin "2") (pinfunction "2_2") (pintype "passive"))
      (node (ref "J3") (pin "19") (pinfunction "19_19") (pintype "bidirectional"))
    )
    (net (code "29") (name "Net-(EPD_C8-Pad2)") (class "Default")
      (node (ref "EPD_C8") (pin "2") (pinfunction "2_2") (pintype "passive"))
      (node (ref "J3") (pin "20") (pinfunction "20_20") (pintype "bidirectional"))
    )
    (net (code "30") (name "Net-(EPD_C10-Pad2)") (class "Default")
      (node (ref "EPD_C10") (pin "2") (pinfunction "2_2") (pintype "passive"))
      (node (ref "J3") (pin "22") (pinfunction "22_22") (pintype "bidirectional"))
    )
    (net (code "31") (name "Net-(EPD_C12-Pad2)") (class "Default")
      (node (ref "EPD_C12") (pin "2") (pinfunction "2_2") (pintype "passive"))
      (node (ref "J3") (pin "24") (pinfunction "24_24") (pintype "bidirectional"))
    )
    (net (code "32") (name "Net-(IC1-CT)") (class "Default")
      (node (ref "C_DELAY") (pin "1") (pinfunction "1_1") (pintype "passive"))
      (node (ref "IC1") (pin "5") (pinfunction "CT_5") (pintype "bidirectional"))
    )
    (net (code "33") (name "Net-(J4-PadA5)") (class "Default")
      (node (ref "J4") (pin "A5") (pinfunction "A5_A5") (pintype "bidirectional"))
      (node (ref "R2-USB1") (pin "2") (pinfunction "2_2") (pintype "passive"))
    )
    (net (code "34") (name "Net-(J4-PadB5)") (class "Default")
      (node (ref "J4") (pin "B5") (pinfunction "B5_B5") (pintype "bidirectional"))
      (node (ref "R2-USB") (pin "1") (pinfunction "1_1") (pintype "passive"))
    )
    (net (code "35") (name "Net-(U4-PROG)") (class "Default")
      (node (ref "R2_BAT") (pin "2") (pinfunction "2_2") (pintype "passive"))
      (node (ref "U4") (pin "5") (pinfunction "PROG_5") (pintype "input"))
    )
    (net (code "36") (name "Net-(U4-STAT)") (class "Default")
      (node (ref "R1_BAT") (pin "2") (pinfunction "2_2") (pintype "passive"))
      (node (ref "U4") (pin "1") (pinfunction "STAT_1") (pintype "output"))
    )
    (net (code "37") (name "PREVGH") (class "Default")
      (node (ref "D10") (pin "1") (pinfunction "K_1") (pintype "bidirectional"))
      (node (ref "EPD_C9") (pin "2") (pinfunction "2_2") (pintype "passive"))
      (node (ref "J3") (pin "21") (pinfunction "21_21") (pintype "bidirectional"))
    )
    (net (code "38") (name "PREVGL") (class "Default")
      (node (ref "D11") (pin "2") (pinfunction "A_2") (pintype "bidirectional"))
      (node (ref "EPD_C11") (pin "2") (pinfunction "2_2") (pintype "passive"))
      (node (ref "J3") (pin "23") (pinfunction "23_23") (pintype "bidirectional"))
    )
    (net (code "39") (name "RESE") (class "Default")
      (node (ref "J3") (pin "3") (pinfunction "3_3") (pintype "bidirectional"))
      (node (ref "Q3") (pin "2") (pinfunction "S_2") (pintype "bidirectional"))
      (node (ref "R12") (pin "2") (pinfunction "2_2") (pintype "passive"))
    )
    (net (code "40") (name "RESE'") (class "Default")
      (node (ref "R12") (pin "1") (pinfunction "1_1") (pintype "passive"))
      (node (ref "R9") (pin "2") (pinfunction "2_2") (pintype "passive"))
      (node (ref "SJ1") (pin "2") (pinfunction "2_2") (pintype "passive"))
    )
    (net (code "41") (name "RESET") (class "Default")
      (node (ref "C3") (pin "1") (pinfunction "1_1") (pintype "passive"))
      (node (ref "IC1") (pin "1") (pinfunction "VOUT_1") (pintype "bidirectional"))
      (node (ref "RESET_BUTTON") (pin "3") (pinfunction "3_3") (pintype "passive"))
      (node (ref "RESET_BUTTON") (pin "4") (pinfunction "4_4") (pintype "passive"))
      (node (ref "R_RESET") (pin "1") (pinfunction "1_1") (pintype "passive"))
      (node (ref "U1") (pin "3") (pinfunction "EN_3") (pintype "input"))
    )
    (net (code "42") (name "RTC_RST") (class "Default")
      (node (ref "U1") (pin "16") (pinfunction "IO18_16") (pintype "bidirectional"))
      (node (ref "U5") (pin "4") (pinfunction "~{RST}_4") (pintype "input"))
    )
    (net (code "43") (name "RX") (class "Default")
      (node (ref "TP2") (pin "TP") (pinfunction "TP_TP") (pintype "input"))
      (node (ref "U1") (pin "24") (pinfunction "RXD0/GPIO17_24") (pintype "bidirectional"))
    )
    (net (code "44") (name "SCK") (class "Default")
      (node (ref "D3") (pin "2") (pinfunction "2_2") (pintype "passive"))
      (node (ref "J1") (pin "P5") (pinfunction "CLK_P5") (pintype "bidirectional"))
      (node (ref "J3") (pin "13") (pinfunction "13_13") (pintype "bidirectional"))
      (node (ref "R5") (pin "1") (pinfunction "1_1") (pintype "passive"))
      (node (ref "TP8") (pin "TP") (pinfunction "TP_TP") (pintype "input"))
      (node (ref "U1") (pin "6") (pinfunction "IO6_6") (pintype "bidirectional"))
      (node (ref "U3") (pin "6") (pinfunction "CLK_6") (pintype "input"))
    )
    (net (code "45") (name "SCL") (class "Default")
      (node (ref "J2") (pin "4") (pinfunction "4_4") (pintype "passive"))
      (node (ref "R2-PINH") (pin "1") (pinfunction "1_1") (pintype "passive"))
      (node (ref "SENSOR2") (pin "4") (pinfunction "SCK_4") (pintype "input"))
      (node (ref "U1") (pin "20") (pinfunction "IO22_20") (pintype "bidirectional"))
      (node (ref "U2") (pin "7") (pinfunction "SCL_7") (pintype "input"))
      (node (ref "U5") (pin "16") (pinfunction "SCL_16") (pintype "input"))
    )
    (net (code "46") (name "SDA") (class "Default")
      (node (ref "J2") (pin "3") (pinfunction "3_3") (pintype "passive"))
      (node (ref "R1_PINH") (pin "1") (pinfunction "1_1") (pintype "passive"))
      (node (ref "SENSOR2") (pin "3") (pinfunction "SDI_3") (pintype "bidirectional"))
      (node (ref "U1") (pin "19") (pinfunction "IO21_19") (pintype "bidirectional"))
      (node (ref "U2") (pin "8") (pinfunction "SDA_8") (pintype "bidirectional"))
      (node (ref "U5") (pin "15") (pinfunction "SDA_15") (pintype "bidirectional"))
    )
    (net (code "47") (name "SRC") (class "Default")
      (node (ref "C19") (pin "2") (pinfunction "2_2") (pintype "passive"))
      (node (ref "D10") (pin "2") (pinfunction "A_2") (pintype "bidirectional"))
      (node (ref "L1") (pin "1") (pinfunction "1_1") (pintype "passive"))
      (node (ref "Q3") (pin "3") (pinfunction "D_3") (pintype "bidirectional"))
    )
    (net (code "48") (name "SS_SD") (class "Default")
      (node (ref "D6") (pin "2") (pinfunction "2_2") (pintype "passive"))
      (node (ref "J1") (pin "P2") (pinfunction "CD/DAT3_P2") (pintype "bidirectional"))
      (node (ref "R2") (pin "1") (pinfunction "1_1") (pintype "passive"))
      (node (ref "U1") (pin "4") (pinfunction "IO4_4") (pintype "bidirectional"))
    )
    (net (code "49") (name "TX") (class "Default")
      (node (ref "TP1") (pin "TP") (pinfunction "TP_TP") (pintype "input"))
      (node (ref "U1") (pin "25") (pinfunction "TXD0/GPIO16_25") (pintype "bidirectional"))
    )
    (net (code "50") (name "USB_D+") (class "Default")
      (node (ref "D12") (pin "1") (pinfunction "I/O1_1_1") (pintype "bidirectional"))
      (node (ref "U1") (pin "14") (pinfunction "IO13_14") (pintype "bidirectional"))
    )
    (net (code "51") (name "USB_D-") (class "Default")
      (node (ref "D12") (pin "3") (pinfunction "I/O2_1_3") (pintype "bidirectional"))
      (node (ref "U1") (pin "13") (pinfunction "IO12_13") (pintype "bidirectional"))
    )
    (net (code "52") (name "VBAT") (class "Default")
      (node (ref "C2_BAT") (pin "1") (pinfunction "1_1") (pintype "passive"))
      (node (ref "Q1") (pin "3") (pinfunction "D_3") (pintype "bidirectional"))
      (node (ref "TP3") (pin "TP") (pinfunction "TP_TP") (pintype "input"))
      (node (ref "U2") (pin "2") (pinfunction "CELL_2") (pintype "power_in"))
      (node (ref "U2") (pin "3") (pinfunction "VDD_3") (pintype "power_in"))
      (node (ref "U4") (pin "3") (pinfunction "VBAT_3") (pintype "power_in"))
    )
    (net (code "53") (name "VBUS") (class "Default")
      (node (ref "C1_BAT") (pin "1") (pinfunction "1_1") (pintype "passive"))
      (node (ref "C4_USB") (pin "1") (pinfunction "1_1") (pintype "passive"))
      (node (ref "C5_USB") (pin "1") (pinfunction "1_1") (pintype "passive"))
      (node (ref "CHG_LED") (pin "A") (pinfunction "A_A") (pintype "passive"))
      (node (ref "D12") (pin "5") (pinfunction "VBUS_5") (pintype "bidirectional"))
      (node (ref "D7") (pin "2") (pinfunction "ANODE_2") (pintype "bidirectional"))
      (node (ref "PFMF.050.1") (pin "2") (pinfunction "2_2") (pintype "passive"))
      (node (ref "Q1") (pin "1") (pinfunction "G_1") (pintype "bidirectional"))
      (node (ref "R1_PWRUSB") (pin "2") (pinfunction "2_2") (pintype "passive"))
      (node (ref "TP14") (pin "TP") (pinfunction "TP_TP") (pintype "input"))
      (node (ref "U4") (pin "4") (pinfunction "VIN_4") (pintype "power_in"))
    )
    (net (code "54") (name "VRTC") (class "Default")
      (node (ref "C10_SUPERCAP") (pin "1") (pinfunction "1_1") (pintype "passive"))
      (node (ref "C8") (pin "1") (pinfunction "1_1") (pintype "passive"))
      (node (ref "R_CAPACITOR") (pin "2") (pinfunction "2_2") (pintype "passive"))
      (node (ref "U5") (pin "14") (pinfunction "VBAT_14") (pintype "power_in"))
    )
    (net (code "55") (name "VUSB") (class "Default")
      (node (ref "J4") (pin "A4") (pinfunction "A4_A4") (pintype "bidirectional"))
      (node (ref "J4") (pin "A9") (pinfunction "A9_A9") (pintype "bidirectional"))
      (node (ref "J4") (pin "B4") (pinfunction "B4_B4") (pintype "bidirectional"))
      (node (ref "J4") (pin "B9") (pinfunction "B9_B9") (pintype "bidirectional"))
      (node (ref "PFMF.050.1") (pin "1") (pinfunction "1_1") (pintype "passive"))
    )
    (net (code "56") (name "unconnected-(IC1-NC-Pad4)") (class "Default")
      (node (ref "IC1") (pin "4") (pinfunction "NC_4") (pintype "no_connect"))
    )
    (net (code "57") (name "unconnected-(IC2-NC-Pad4)") (class "Default")
      (node (ref "IC2") (pin "4") (pinfunction "NC_4") (pintype "no_connect"))
    )
    (net (code "58") (name "unconnected-(J1-DAT1-PadP8)") (class "Default")
      (node (ref "J1") (pin "P8") (pinfunction "DAT1_P8") (pintype "bidirectional"))
    )
    (net (code "59") (name "unconnected-(J1-DAT2-PadP1)") (class "Default")
      (node (ref "J1") (pin "P1") (pinfunction "DAT2_P1") (pintype "bidirectional"))
    )
    (net (code "60") (name "unconnected-(J1-DETECTION_1-PadS1)") (class "Default")
      (node (ref "J1") (pin "S1") (pinfunction "DETECTION_1_S1") (pintype "bidirectional"))
    )
    (net (code "61") (name "unconnected-(J1-DETECTION_2-PadS2)") (class "Default")
      (node (ref "J1") (pin "S2") (pinfunction "DETECTION_2_S2") (pintype "bidirectional"))
    )
    (net (code "62") (name "unconnected-(J3-Pad1)") (class "Default")
      (node (ref "J3") (pin "1") (pinfunction "1_1") (pintype "bidirectional"))
    )
    (net (code "63") (name "unconnected-(J3-Pad6)") (class "Default")
      (node (ref "J3") (pin "6") (pinfunction "6_6") (pintype "bidirectional"))
    )
    (net (code "64") (name "unconnected-(J3-Pad7)") (class "Default")
      (node (ref "J3") (pin "7") (pinfunction "7_7") (pintype "bidirectional"))
    )
    (net (code "65") (name "unconnected-(J4-PadA8)") (class "Default")
      (node (ref "J4") (pin "A8") (pinfunction "A8_A8") (pintype "bidirectional"))
    )
    (net (code "66") (name "unconnected-(J4-PadB8)") (class "Default")
      (node (ref "J4") (pin "B8") (pinfunction "B8_B8") (pintype "bidirectional"))
    )
    (net (code "67") (name "unconnected-(U1-NC-Pad22)") (class "Default")
      (node (ref "U1") (pin "22") (pinfunction "NC_22") (pintype "no_connect"))
    )
    (net (code "68") (name "unconnected-(U2-~{ALERT}-Pad5)") (class "Default")
      (node (ref "U2") (pin "5") (pinfunction "~{ALERT}_5") (pintype "output"))
    )
  )
)
